# esp32buscam_03.net
KiCad netlist of a schematic drawn in EAGLE
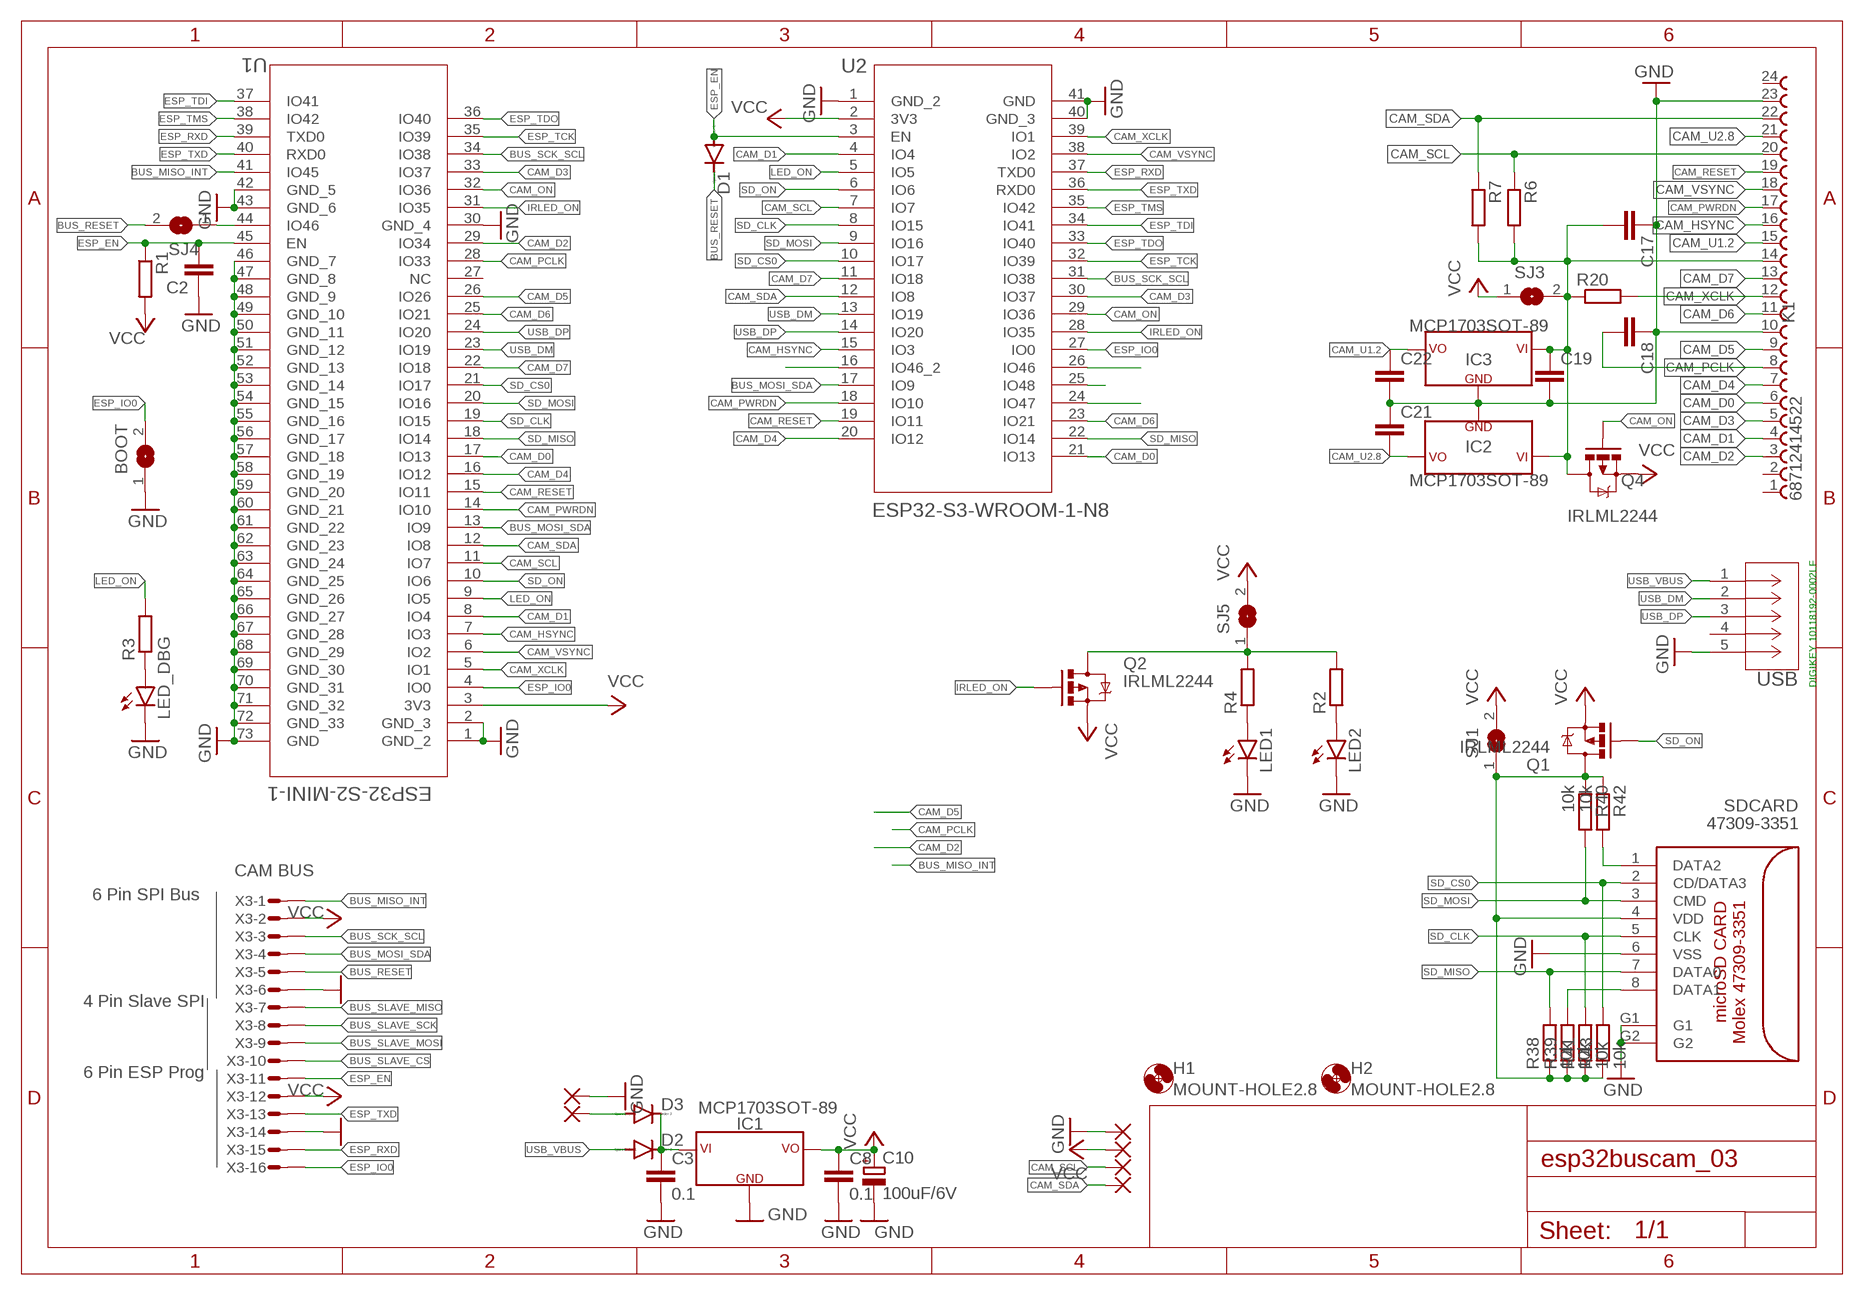
[diagram p0: schematic, sheet 1]

(export (version "E")
  (design (tool "Eeschema 10.0.6"))
  (components
    (comp (ref "BOOT")
      (value "SJ")
      (footprint "eagle-import:SJ")
      (libsource (lib "eagle-import") (part "SJ"))
    )
    (comp (ref "C2")
      (value "C-EUC0603")
      (footprint "eagle-import:C0603")
      (libsource (lib "eagle-import") (part "rcl_334_C-EUC0603"))
    )
    (comp (ref "C3")
      (value "0.1")
      (footprint "eagle-import:C0805")
      (libsource (lib "eagle-import") (part "C-EUC0805"))
    )
    (comp (ref "C8")
      (value "0.1")
      (footprint "eagle-import:C0805")
      (libsource (lib "eagle-import") (part "C-EUC0805"))
    )
    (comp (ref "C10")
      (value "100uF/6V")
      (footprint "eagle-import:B_3528-21R")
      (libsource (lib "eagle-import") (part "CPOL-EUB/3528-21R"))
    )
    (comp (ref "C17")
      (value "C-EUC0603")
      (footprint "eagle-import:C0603")
      (libsource (lib "eagle-import") (part "rcl_334_C-EUC0603"))
    )
    (comp (ref "C18")
      (value "C-EUC0603")
      (footprint "eagle-import:C0603")
      (libsource (lib "eagle-import") (part "rcl_334_C-EUC0603"))
    )
    (comp (ref "C19")
      (value "C-EUC0603")
      (footprint "eagle-import:C0603")
      (libsource (lib "eagle-import") (part "rcl_334_C-EUC0603"))
    )
    (comp (ref "C21")
      (value "C-EUC0603")
      (footprint "eagle-import:C0603")
      (libsource (lib "eagle-import") (part "rcl_334_C-EUC0603"))
    )
    (comp (ref "C22")
      (value "C-EUC0603")
      (footprint "eagle-import:C0603")
      (libsource (lib "eagle-import") (part "rcl_334_C-EUC0603"))
    )
    (comp (ref "D1")
      (value "DIODE-MINIMELF")
      (footprint "eagle-import:MINIMELF")
      (libsource (lib "eagle-import") (part "DIODE-MINIMELF"))
    )
    (comp (ref "D2")
      (value "DIODE-MINIMELF")
      (footprint "eagle-import:MINIMELF")
      (libsource (lib "eagle-import") (part "DIODE-MINIMELF"))
    )
    (comp (ref "D3")
      (value "DIODE-MINIMELF")
      (footprint "eagle-import:MINIMELF")
      (libsource (lib "eagle-import") (part "DIODE-MINIMELF"))
    )
    (comp (ref "H1")
      (value "MOUNT-HOLE2.8")
      (footprint "eagle-import:2,8")
      (libsource (lib "eagle-import") (part "MOUNT-HOLE2.8"))
    )
    (comp (ref "H2")
      (value "MOUNT-HOLE2.8")
      (footprint "eagle-import:2,8")
      (libsource (lib "eagle-import") (part "MOUNT-HOLE2.8"))
    )
    (comp (ref "IC1")
      (value "MCP1703SOT-89")
      (footprint "eagle-import:SOT89")
      (libsource (lib "eagle-import") (part "MCP1703SOT-89"))
    )
    (comp (ref "IC2")
      (value "MCP1703SOT-89")
      (footprint "eagle-import:SOT89")
      (libsource (lib "eagle-import") (part "MCP1703SOT-89"))
    )
    (comp (ref "IC3")
      (value "MCP1703SOT-89")
      (footprint "eagle-import:SOT89")
      (libsource (lib "eagle-import") (part "MCP1703SOT-89"))
    )
    (comp (ref "K1")
      (value "68712414522")
      (footprint "eagle-import:68712414522")
      (libsource (lib "eagle-import") (part "68712414522"))
    )
    (comp (ref "LED1")
      (value "LED5MM")
      (footprint "eagle-import:LED5MM")
      (libsource (lib "eagle-import") (part "LED5MM"))
    )
    (comp (ref "LED2")
      (value "LED5MM")
      (footprint "eagle-import:LED5MM")
      (libsource (lib "eagle-import") (part "LED5MM"))
    )
    (comp (ref "LED_DBG")
      (value "G")
      (footprint "eagle-import:CHIPLED_0805")
      (libsource (lib "eagle-import") (part "LEDCHIPLED_0805"))
    )
    (comp (ref "PAD1")
      (value "1,6/0,9")
      (footprint "eagle-import:1,6_0,9")
      (libsource (lib "eagle-import") (part "1,6/0,9"))
    )
    (comp (ref "PAD2")
      (value "1,6/0,9")
      (footprint "eagle-import:1,6_0,9")
      (libsource (lib "eagle-import") (part "1,6/0,9"))
    )
    (comp (ref "PAD3")
      (value "1,6/0,9")
      (footprint "eagle-import:1,6_0,9")
      (libsource (lib "eagle-import") (part "1,6/0,9"))
    )
    (comp (ref "PAD4")
      (value "1,6/0,9")
      (footprint "eagle-import:1,6_0,9")
      (libsource (lib "eagle-import") (part "1,6/0,9"))
    )
    (comp (ref "PAD5")
      (value "1,6/0,9")
      (footprint "eagle-import:1,6_0,9")
      (libsource (lib "eagle-import") (part "1,6/0,9"))
    )
    (comp (ref "PAD6")
      (value "1,6/0,9")
      (footprint "eagle-import:1,6_0,9")
      (libsource (lib "eagle-import") (part "1,6/0,9"))
    )
    (comp (ref "Q1")
      (value "IRLML2244")
      (footprint "eagle-import:SOT23-3")
      (libsource (lib "eagle-import") (part "MOSFET-PCHANNELIRLML2244"))
    )
    (comp (ref "Q2")
      (value "IRLML2244")
      (footprint "eagle-import:SOT23-3")
      (libsource (lib "eagle-import") (part "MOSFET-PCHANNELIRLML2244"))
    )
    (comp (ref "Q4")
      (value "IRLML2244")
      (footprint "eagle-import:SOT23-3")
      (libsource (lib "eagle-import") (part "MOSFET-PCHANNELIRLML2244"))
    )
    (comp (ref "R1")
      (value "R-EU_R0603")
      (footprint "eagle-import:R0603")
      (libsource (lib "eagle-import") (part "rcl_334_R-EU_R0603"))
    )
    (comp (ref "R2")
      (value "R-EU_R0402")
      (footprint "eagle-import:R0402")
      (libsource (lib "eagle-import") (part "rcl_334_R-EU_R0402"))
    )
    (comp (ref "R3")
      (value "R-EU_R0402")
      (footprint "eagle-import:R0402")
      (libsource (lib "eagle-import") (part "rcl_334_R-EU_R0402"))
    )
    (comp (ref "R4")
      (value "R-EU_R0402")
      (footprint "eagle-import:R0402")
      (libsource (lib "eagle-import") (part "rcl_334_R-EU_R0402"))
    )
    (comp (ref "R6")
      (value "R-EU_R0603")
      (footprint "eagle-import:R0603")
      (libsource (lib "eagle-import") (part "rcl_334_R-EU_R0603"))
    )
    (comp (ref "R7")
      (value "R-EU_R0603")
      (footprint "eagle-import:R0603")
      (libsource (lib "eagle-import") (part "rcl_334_R-EU_R0603"))
    )
    (comp (ref "R20")
      (value "R-EU_R0603")
      (footprint "eagle-import:R0603")
      (libsource (lib "eagle-import") (part "rcl_334_R-EU_R0603"))
    )
    (comp (ref "R38")
      (value "10k")
      (footprint "eagle-import:R0805")
      (libsource (lib "eagle-import") (part "R-EU_R0805"))
    )
    (comp (ref "R39")
      (value "10k")
      (footprint "eagle-import:R0805")
      (libsource (lib "eagle-import") (part "R-EU_R0805"))
    )
    (comp (ref "R40")
      (value "10k")
      (footprint "eagle-import:R0805")
      (libsource (lib "eagle-import") (part "R-EU_R0805"))
    )
    (comp (ref "R41")
      (value "10k")
      (footprint "eagle-import:R0805")
      (libsource (lib "eagle-import") (part "R-EU_R0805"))
    )
    (comp (ref "R42")
      (value "10k")
      (footprint "eagle-import:R0805")
      (libsource (lib "eagle-import") (part "R-EU_R0805"))
    )
    (comp (ref "R43")
      (value "10k")
      (footprint "eagle-import:R0805")
      (libsource (lib "eagle-import") (part "R-EU_R0805"))
    )
    (comp (ref "SDCARD")
      (value "47309-3351")
      (footprint "eagle-import:47309-3351")
      (libsource (lib "eagle-import") (part "47309-3351"))
    )
    (comp (ref "SJ1") (value "SJ") (footprint "eagle-import:SJ") (libsource (lib "eagle-import") (part "SJ")))
    (comp (ref "SJ3") (value "SJ") (footprint "eagle-import:SJ") (libsource (lib "eagle-import") (part "SJ")))
    (comp (ref "SJ4") (value "SJ") (footprint "eagle-import:SJ") (libsource (lib "eagle-import") (part "SJ")))
    (comp (ref "SJ5") (value "SJ") (footprint "eagle-import:SJ") (libsource (lib "eagle-import") (part "SJ")))
    (comp (ref "U1")
      (value "ESP32-S2-MINI-1")
      (footprint "eagle-import:QFN60_ESP32-S2-MINI-1_EXP")
      (fields (field (name "COPYRIGHT") "Copyright (C) 2018 Accelerated Designs. All rights reserved"))
      (libsource (lib "eagle-import") (part "ESP32-S2-MINI-1"))
    )
    (comp (ref "U2")
      (value "ESP32-S3-WROOM-1-N8")
      (footprint "eagle-import:ESP32-S3-WROOM-1-N8_EXP")
      (fields (field (name "COPYRIGHT") "Copyright (C) 2021 Ultra Librarian. All rights reserved."))
      (libsource (lib "eagle-import") (part "ESP32-S3-WROOM-1-N8"))
    )
    (comp (ref "USB")
      (value "10118192-0002LF")
      (footprint "eagle-import:CONN_10118192-0002LF_AMP")
      (fields (field (name "COPYRIGHT") "Copyright (C) 2018 Accelerated Designs. All rights reserved"))
      (libsource (lib "eagle-import") (part "10118192-0002LF"))
    )
    (comp (ref "X3")
      (value "CAM BUS")
      (footprint "eagle-import:MICROMATCH-16SMD")
      (libsource (lib "eagle-import") (part "MICROMATCH-16SMD"))
    )
  )
  (nets
    (net (code "1") (name "BUS_MISO_INT") (class "Default")
      (node (ref "U1") (pin "41") (pinfunction "IO45_41") (pintype "bidirectional"))
      (node (ref "X3") (pin "16") (pinfunction "S_16") (pintype "passive"))
    )
    (net (code "2") (name "BUS_MOSI_SDA") (class "Default")
      (node (ref "U1") (pin "13") (pinfunction "IO9_13") (pintype "bidirectional"))
      (node (ref "U2") (pin "17") (pinfunction "IO9_17") (pintype "passive"))
      (node (ref "X3") (pin "13") (pinfunction "S_13") (pintype "passive"))
    )
    (net (code "3") (name "BUS_RESET") (class "Default")
      (node (ref "D1") (pin "C") (pinfunction "C_C") (pintype "passive"))
      (node (ref "SJ4") (pin "2") (pinfunction "2_2") (pintype "passive"))
      (node (ref "X3") (pin "12") (pinfunction "S_12") (pintype "passive"))
    )
    (net (code "4") (name "BUS_SCK_SCL") (class "Default")
      (node (ref "U1") (pin "34") (pinfunction "IO38_34") (pintype "bidirectional"))
      (node (ref "U2") (pin "31") (pinfunction "IO38_31") (pintype "passive"))
      (node (ref "X3") (pin "14") (pinfunction "S_14") (pintype "passive"))
    )
    (net (code "5") (name "BUS_SLAVE_CS") (class "Default")
      (node (ref "X3") (pin "7") (pinfunction "S_7") (pintype "passive"))
    )
    (net (code "6") (name "BUS_SLAVE_MISO") (class "Default")
      (node (ref "X3") (pin "10") (pinfunction "S_10") (pintype "passive"))
    )
    (net (code "7") (name "BUS_SLAVE_MOSI") (class "Default")
      (node (ref "X3") (pin "8") (pinfunction "S_8") (pintype "passive"))
    )
    (net (code "8") (name "BUS_SLAVE_SCK") (class "Default")
      (node (ref "X3") (pin "9") (pinfunction "S_9") (pintype "passive"))
    )
    (net (code "9") (name "CAM_D0") (class "Default")
      (node (ref "K1") (pin "6") (pinfunction "6_6") (pintype "passive"))
      (node (ref "U1") (pin "17") (pinfunction "IO13_17") (pintype "bidirectional"))
      (node (ref "U2") (pin "21") (pinfunction "IO13_21") (pintype "passive"))
    )
    (net (code "10") (name "CAM_D1") (class "Default")
      (node (ref "K1") (pin "4") (pinfunction "4_4") (pintype "passive"))
      (node (ref "U1") (pin "8") (pinfunction "IO4_8") (pintype "bidirectional"))
      (node (ref "U2") (pin "4") (pinfunction "IO4_4") (pintype "passive"))
    )
    (net (code "11") (name "CAM_D2") (class "Default")
      (node (ref "K1") (pin "3") (pinfunction "3_3") (pintype "passive"))
      (node (ref "U1") (pin "29") (pinfunction "IO34_29") (pintype "bidirectional"))
    )
    (net (code "12") (name "CAM_D3") (class "Default")
      (node (ref "K1") (pin "5") (pinfunction "5_5") (pintype "passive"))
      (node (ref "U1") (pin "33") (pinfunction "IO37_33") (pintype "bidirectional"))
      (node (ref "U2") (pin "30") (pinfunction "IO37_30") (pintype "passive"))
    )
    (net (code "13") (name "CAM_D4") (class "Default")
      (node (ref "K1") (pin "7") (pinfunction "7_7") (pintype "passive"))
      (node (ref "U1") (pin "16") (pinfunction "IO12_16") (pintype "bidirectional"))
      (node (ref "U2") (pin "20") (pinfunction "IO12_20") (pintype "passive"))
    )
    (net (code "14") (name "CAM_D5") (class "Default")
      (node (ref "K1") (pin "9") (pinfunction "9_9") (pintype "passive"))
      (node (ref "U1") (pin "26") (pinfunction "IO26_26") (pintype "bidirectional"))
    )
    (net (code "15") (name "CAM_D6") (class "Default")
      (node (ref "K1") (pin "11") (pinfunction "11_11") (pintype "passive"))
      (node (ref "U1") (pin "25") (pinfunction "IO21_25") (pintype "bidirectional"))
      (node (ref "U2") (pin "23") (pinfunction "IO21_23") (pintype "passive"))
    )
    (net (code "16") (name "CAM_D7") (class "Default")
      (node (ref "K1") (pin "13") (pinfunction "13_13") (pintype "passive"))
      (node (ref "U1") (pin "22") (pinfunction "IO18_22") (pintype "bidirectional"))
      (node (ref "U2") (pin "11") (pinfunction "IO18_11") (pintype "passive"))
    )
    (net (code "17") (name "CAM_HSYNC") (class "Default")
      (node (ref "K1") (pin "16") (pinfunction "16_16") (pintype "passive"))
      (node (ref "U1") (pin "7") (pinfunction "IO3_7") (pintype "bidirectional"))
      (node (ref "U2") (pin "15") (pinfunction "IO3_15") (pintype "passive"))
    )
    (net (code "18") (name "CAM_ON") (class "Default")
      (node (ref "Q4") (pin "1") (pinfunction "G_1") (pintype "passive"))
      (node (ref "U1") (pin "32") (pinfunction "IO36_32") (pintype "bidirectional"))
      (node (ref "U2") (pin "29") (pinfunction "IO36_29") (pintype "passive"))
    )
    (net (code "19") (name "CAM_PCLK") (class "Default")
      (node (ref "C18") (pin "2") (pinfunction "2_2") (pintype "passive"))
      (node (ref "K1") (pin "8") (pinfunction "8_8") (pintype "passive"))
      (node (ref "U1") (pin "28") (pinfunction "IO33_28") (pintype "bidirectional"))
    )
    (net (code "20") (name "CAM_PWRDN") (class "Default")
      (node (ref "K1") (pin "17") (pinfunction "17_17") (pintype "passive"))
      (node (ref "U1") (pin "14") (pinfunction "IO10_14") (pintype "bidirectional"))
      (node (ref "U2") (pin "18") (pinfunction "IO10_18") (pintype "passive"))
    )
    (net (code "21") (name "CAM_RESET") (class "Default")
      (node (ref "K1") (pin "19") (pinfunction "19_19") (pintype "passive"))
      (node (ref "U1") (pin "15") (pinfunction "IO11_15") (pintype "bidirectional"))
      (node (ref "U2") (pin "19") (pinfunction "IO11_19") (pintype "passive"))
    )
    (net (code "22") (name "CAM_SCL") (class "Default")
      (node (ref "K1") (pin "20") (pinfunction "20_20") (pintype "passive"))
      (node (ref "PAD3") (pin "1") (pinfunction "P_1") (pintype "passive"))
      (node (ref "R6") (pin "1") (pinfunction "1_1") (pintype "passive"))
      (node (ref "U1") (pin "11") (pinfunction "IO7_11") (pintype "bidirectional"))
      (node (ref "U2") (pin "7") (pinfunction "IO7_7") (pintype "passive"))
    )
    (net (code "23") (name "CAM_SDA") (class "Default")
      (node (ref "K1") (pin "22") (pinfunction "22_22") (pintype "passive"))
      (node (ref "PAD4") (pin "1") (pinfunction "P_1") (pintype "passive"))
      (node (ref "R7") (pin "1") (pinfunction "1_1") (pintype "passive"))
      (node (ref "U1") (pin "12") (pinfunction "IO8_12") (pintype "bidirectional"))
      (node (ref "U2") (pin "12") (pinfunction "IO8_12") (pintype "passive"))
    )
    (net (code "24") (name "CAM_U1.2") (class "Default")
      (node (ref "C22") (pin "1") (pinfunction "1_1") (pintype "passive"))
      (node (ref "IC3") (pin "3") (pinfunction "VCC_3") (pintype "power_in"))
      (node (ref "K1") (pin "15") (pinfunction "15_15") (pintype "passive"))
    )
    (net (code "25") (name "CAM_U2.8") (class "Default")
      (node (ref "C21") (pin "2") (pinfunction "2_2") (pintype "passive"))
      (node (ref "IC2") (pin "3") (pinfunction "VCC_3") (pintype "power_in"))
      (node (ref "K1") (pin "21") (pinfunction "21_21") (pintype "passive"))
    )
    (net (code "26") (name "CAM_VSYNC") (class "Default")
      (node (ref "K1") (pin "18") (pinfunction "18_18") (pintype "passive"))
      (node (ref "U1") (pin "6") (pinfunction "IO2_6") (pintype "bidirectional"))
      (node (ref "U2") (pin "38") (pinfunction "IO2_38") (pintype "passive"))
    )
    (net (code "27") (name "CAM_XCLK") (class "Default")
      (node (ref "K1") (pin "12") (pinfunction "12_12") (pintype "passive"))
      (node (ref "R20") (pin "2") (pinfunction "2_2") (pintype "passive"))
      (node (ref "U1") (pin "5") (pinfunction "IO1_5") (pintype "bidirectional"))
      (node (ref "U2") (pin "39") (pinfunction "IO1_39") (pintype "passive"))
    )
    (net (code "28") (name "ESP_EN") (class "Default")
      (node (ref "C2") (pin "2") (pinfunction "2_2") (pintype "passive"))
      (node (ref "D1") (pin "A") (pinfunction "A_A") (pintype "passive"))
      (node (ref "R1") (pin "1") (pinfunction "1_1") (pintype "passive"))
      (node (ref "U1") (pin "45") (pinfunction "EN_45") (pintype "passive"))
      (node (ref "U2") (pin "3") (pinfunction "EN_3") (pintype "passive"))
      (node (ref "X3") (pin "6") (pinfunction "S_6") (pintype "passive"))
    )
    (net (code "29") (name "ESP_IO0") (class "Default")
      (node (ref "BOOT") (pin "2") (pinfunction "2_2") (pintype "passive"))
      (node (ref "U1") (pin "4") (pinfunction "IO0_4") (pintype "bidirectional"))
      (node (ref "U2") (pin "27") (pinfunction "IO0_27") (pintype "passive"))
      (node (ref "X3") (pin "1") (pinfunction "S_1") (pintype "passive"))
    )
    (net (code "30") (name "ESP_RXD") (class "Default")
      (node (ref "U1") (pin "39") (pinfunction "TXD0_39") (pintype "bidirectional"))
      (node (ref "U2") (pin "37") (pinfunction "TXD0_37") (pintype "passive"))
      (node (ref "X3") (pin "2") (pinfunction "S_2") (pintype "passive"))
    )
    (net (code "31") (name "ESP_TCK") (class "Default")
      (node (ref "U1") (pin "35") (pinfunction "IO39_35") (pintype "bidirectional"))
      (node (ref "U2") (pin "32") (pinfunction "IO39_32") (pintype "passive"))
    )
    (net (code "32") (name "ESP_TDI") (class "Default")
      (node (ref "U1") (pin "37") (pinfunction "IO41_37") (pintype "bidirectional"))
      (node (ref "U2") (pin "34") (pinfunction "IO41_34") (pintype "passive"))
    )
    (net (code "33") (name "ESP_TDO") (class "Default")
      (node (ref "U1") (pin "36") (pinfunction "IO40_36") (pintype "bidirectional"))
      (node (ref "U2") (pin "33") (pinfunction "IO40_33") (pintype "passive"))
    )
    (net (code "34") (name "ESP_TMS") (class "Default")
      (node (ref "U1") (pin "38") (pinfunction "IO42_38") (pintype "bidirectional"))
      (node (ref "U2") (pin "35") (pinfunction "IO42_35") (pintype "passive"))
    )
    (net (code "35") (name "ESP_TXD") (class "Default")
      (node (ref "U1") (pin "40") (pinfunction "RXD0_40") (pintype "bidirectional"))
      (node (ref "U2") (pin "36") (pinfunction "RXD0_36") (pintype "passive"))
      (node (ref "X3") (pin "4") (pinfunction "S_4") (pintype "passive"))
    )
    (net (code "36") (name "GND") (class "Default")
      (node (ref "BOOT") (pin "1") (pinfunction "1_1") (pintype "passive"))
      (node (ref "C10") (pin "-") (pinfunction "-_-") (pintype "passive"))
      (node (ref "C17") (pin "1") (pinfunction "1_1") (pintype "passive"))
      (node (ref "C18") (pin "1") (pinfunction "1_1") (pintype "passive"))
      (node (ref "C19") (pin "2") (pinfunction "2_2") (pintype "passive"))
      (node (ref "C2") (pin "1") (pinfunction "1_1") (pintype "passive"))
      (node (ref "C21") (pin "1") (pinfunction "1_1") (pintype "passive"))
      (node (ref "C22") (pin "2") (pinfunction "2_2") (pintype "passive"))
      (node (ref "C3") (pin "2") (pinfunction "2_2") (pintype "passive"))
      (node (ref "C8") (pin "2") (pinfunction "2_2") (pintype "passive"))
      (node (ref "IC1") (pin "1") (pinfunction "GND_1") (pintype "power_in"))
      (node (ref "IC2") (pin "1") (pinfunction "GND_1") (pintype "power_in"))
      (node (ref "IC3") (pin "1") (pinfunction "GND_1") (pintype "power_in"))
      (node (ref "K1") (pin "10") (pinfunction "10_10") (pintype "passive"))
      (node (ref "K1") (pin "23") (pinfunction "23_23") (pintype "passive"))
      (node (ref "LED1") (pin "K") (pinfunction "C_K") (pintype "passive"))
      (node (ref "LED2") (pin "K") (pinfunction "C_K") (pintype "passive"))
      (node (ref "LED_DBG") (pin "C") (pinfunction "C_C") (pintype "passive"))
      (node (ref "PAD1") (pin "1") (pinfunction "P_1") (pintype "passive"))
      (node (ref "PAD6") (pin "1") (pinfunction "P_1") (pintype "passive"))
      (node (ref "SDCARD") (pin "6") (pinfunction "VSS_6") (pintype "bidirectional"))
      (node (ref "SDCARD") (pin "G1") (pinfunction "G1_G1") (pintype "bidirectional"))
      (node (ref "SDCARD") (pin "G2") (pinfunction "G2_G2") (pintype "bidirectional"))
      (node (ref "U1") (pin "1") (pinfunction "GND_2_1") (pintype "passive"))
      (node (ref "U1") (pin "2") (pinfunction "GND_3_2") (pintype "passive"))
      (node (ref "U1") (pin "30") (pinfunction "GND_4_30") (pintype "passive"))
      (node (ref "U1") (pin "42") (pinfunction "GND_5_42") (pintype "passive"))
      (node (ref "U1") (pin "43") (pinfunction "GND_6_43") (pintype "passive"))
      (node (ref "U1") (pin "46") (pinfunction "GND_7_46") (pintype "passive"))
      (node (ref "U1") (pin "47") (pinfunction "GND_8_47") (pintype "passive"))
      (node (ref "U1") (pin "48") (pinfunction "GND_9_48") (pintype "passive"))
      (node (ref "U1") (pin "49") (pinfunction "GND_10_49") (pintype "passive"))
      (node (ref "U1") (pin "50") (pinfunction "GND_11_50") (pintype "passive"))
      (node (ref "U1") (pin "51") (pinfunction "GND_12_51") (pintype "passive"))
      (node (ref "U1") (pin "52") (pinfunction "GND_13_52") (pintype "passive"))
      (node (ref "U1") (pin "53") (pinfunction "GND_14_53") (pintype "passive"))
      (node (ref "U1") (pin "54") (pinfunction "GND_15_54") (pintype "passive"))
      (node (ref "U1") (pin "55") (pinfunction "GND_16_55") (pintype "passive"))
      (node (ref "U1") (pin "56") (pinfunction "GND_17_56") (pintype "passive"))
      (node (ref "U1") (pin "57") (pinfunction "GND_18_57") (pintype "passive"))
      (node (ref "U1") (pin "58") (pinfunction "GND_19_58") (pintype "passive"))
      (node (ref "U1") (pin "59") (pinfunction "GND_20_59") (pintype "passive"))
      (node (ref "U1") (pin "60") (pinfunction "GND_21_60") (pintype "passive"))
      (node (ref "U1") (pin "61") (pinfunction "GND_22_61") (pintype "passive"))
      (node (ref "U1") (pin "62") (pinfunction "GND_23_62") (pintype "passive"))
      (node (ref "U1") (pin "63") (pinfunction "GND_24_63") (pintype "passive"))
      (node (ref "U1") (pin "64") (pinfunction "GND_25_64") (pintype "passive"))
      (node (ref "U1") (pin "65") (pinfunction "GND_26_65") (pintype "passive"))
      (node (ref "U1") (pin "66") (pinfunction "GND_27_66") (pintype "passive"))
      (node (ref "U1") (pin "67") (pinfunction "GND_28_67") (pintype "passive"))
      (node (ref "U1") (pin "68") (pinfunction "GND_29_68") (pintype "passive"))
      (node (ref "U1") (pin "69") (pinfunction "GND_30_69") (pintype "passive"))
      (node (ref "U1") (pin "70") (pinfunction "GND_31_70") (pintype "passive"))
      (node (ref "U1") (pin "71") (pinfunction "GND_32_71") (pintype "passive"))
      (node (ref "U1") (pin "72") (pinfunction "GND_33_72") (pintype "passive"))
      (node (ref "U1") (pin "73") (pinfunction "GND_73") (pintype "passive"))
      (node (ref "U2") (pin "1") (pinfunction "GND_2_1") (pintype "passive"))
      (node (ref "U2") (pin "40") (pinfunction "GND_3_40") (pintype "passive"))
      (node (ref "U2") (pin "41") (pinfunction "GND_41") (pintype "passive"))
      (node (ref "USB") (pin "5") (pinfunction "5_5") (pintype "passive"))
      (node (ref "X3") (pin "11") (pinfunction "S_11") (pintype "passive"))
      (node (ref "X3") (pin "3") (pinfunction "S_3") (pintype "passive"))
    )
    (net (code "37") (name "IRLED_ON") (class "Default")
      (node (ref "Q2") (pin "1") (pinfunction "G_1") (pintype "passive"))
      (node (ref "U1") (pin "31") (pinfunction "IO35_31") (pintype "bidirectional"))
      (node (ref "U2") (pin "28") (pinfunction "IO35_28") (pintype "passive"))
    )
    (net (code "38") (name "LED_ON") (class "Default")
      (node (ref "R3") (pin "2") (pinfunction "2_2") (pintype "passive"))
      (node (ref "U1") (pin "9") (pinfunction "IO5_9") (pintype "bidirectional"))
      (node (ref "U2") (pin "5") (pinfunction "IO5_5") (pintype "passive"))
    )
    (net (code "39") (name "Net-(C3-Pad1)") (class "Default")
      (node (ref "C3") (pin "1") (pinfunction "1_1") (pintype "passive"))
      (node (ref "D2") (pin "C") (pinfunction "C_C") (pintype "passive"))
      (node (ref "D3") (pin "C") (pinfunction "C_C") (pintype "passive"))
      (node (ref "IC1") (pin "2") (pinfunction "VIN_2") (pintype "power_in"))
      (node (ref "IC1") (pin "4") (pinfunction "VIN_4") (pintype "power_in"))
    )
    (net (code "40") (name "Net-(LED1-PadA)") (class "Default")
      (node (ref "LED1") (pin "A") (pinfunction "A_A") (pintype "passive"))
      (node (ref "R4") (pin "1") (pinfunction "1_1") (pintype "passive"))
    )
    (net (code "41") (name "Net-(LED2-PadA)") (class "Default")
      (node (ref "LED2") (pin "A") (pinfunction "A_A") (pintype "passive"))
      (node (ref "R2") (pin "1") (pinfunction "1_1") (pintype "passive"))
    )
    (net (code "42") (name "Net-(LED_DBG-PadA)") (class "Default")
      (node (ref "LED_DBG") (pin "A") (pinfunction "A_A") (pintype "passive"))
      (node (ref "R3") (pin "1") (pinfunction "1_1") (pintype "passive"))
    )
    (net (code "43") (name "Net-(PAD5-P)") (class "Default")
      (node (ref "D3") (pin "A") (pinfunction "A_A") (pintype "passive"))
      (node (ref "PAD5") (pin "1") (pinfunction "P_1") (pintype "passive"))
    )
    (net (code "44") (name "Net-(Q1-D)") (class "Default")
      (node (ref "Q1") (pin "3") (pinfunction "D_3") (pintype "passive"))
      (node (ref "R38") (pin "1") (pinfunction "1_1") (pintype "passive"))
      (node (ref "R39") (pin "1") (pinfunction "1_1") (pintype "passive"))
      (node (ref "R40") (pin "1") (pinfunction "1_1") (pintype "passive"))
      (node (ref "R41") (pin "1") (pinfunction "1_1") (pintype "passive"))
      (node (ref "R42") (pin "1") (pinfunction "1_1") (pintype "passive"))
      (node (ref "R43") (pin "1") (pinfunction "1_1") (pintype "passive"))
      (node (ref "SDCARD") (pin "4") (pinfunction "VDD_4") (pintype "bidirectional"))
      (node (ref "SJ1") (pin "1") (pinfunction "1_1") (pintype "passive"))
    )
    (net (code "45") (name "Net-(Q2-D)") (class "Default")
      (node (ref "Q2") (pin "3") (pinfunction "D_3") (pintype "passive"))
      (node (ref "R2") (pin "2") (pinfunction "2_2") (pintype "passive"))
      (node (ref "R4") (pin "2") (pinfunction "2_2") (pintype "passive"))
      (node (ref "SJ5") (pin "1") (pinfunction "1_1") (pintype "passive"))
    )
    (net (code "46") (name "Net-(Q4-D)") (class "Default")
      (node (ref "C17") (pin "2") (pinfunction "2_2") (pintype "passive"))
      (node (ref "C19") (pin "1") (pinfunction "1_1") (pintype "passive"))
      (node (ref "IC2") (pin "2") (pinfunction "VIN_2") (pintype "power_in"))
      (node (ref "IC2") (pin "4") (pinfunction "VIN_4") (pintype "power_in"))
      (node (ref "IC3") (pin "2") (pinfunction "VIN_2") (pintype "power_in"))
      (node (ref "IC3") (pin "4") (pinfunction "VIN_4") (pintype "power_in"))
      (node (ref "K1") (pin "14") (pinfunction "14_14") (pintype "passive"))
      (node (ref "Q4") (pin "3") (pinfunction "D_3") (pintype "passive"))
      (node (ref "R20") (pin "1") (pinfunction "1_1") (pintype "passive"))
      (node (ref "R6") (pin "2") (pinfunction "2_2") (pintype "passive"))
      (node (ref "R7") (pin "2") (pinfunction "2_2") (pintype "passive"))
      (node (ref "SJ3") (pin "2") (pinfunction "2_2") (pintype "passive"))
    )
    (net (code "47") (name "Net-(SDCARD-DATA1)") (class "Default")
      (node (ref "R39") (pin "2") (pinfunction "2_2") (pintype "passive"))
      (node (ref "SDCARD") (pin "8") (pinfunction "DATA1_8") (pintype "bidirectional"))
    )
    (net (code "48") (name "Net-(SDCARD-DATA2)") (class "Default")
      (node (ref "R42") (pin "2") (pinfunction "2_2") (pintype "passive"))
      (node (ref "SDCARD") (pin "1") (pinfunction "DATA2_1") (pintype "bidirectional"))
    )
    (net (code "49") (name "Net-(U1-IO46)") (class "Default")
      (node (ref "SJ4") (pin "1") (pinfunction "1_1") (pintype "passive"))
      (node (ref "U1") (pin "44") (pinfunction "IO46_44") (pintype "bidirectional"))
    )
    (net (code "50") (name "SD_CLK") (class "Default")
      (node (ref "R41") (pin "2") (pinfunction "2_2") (pintype "passive"))
      (node (ref "SDCARD") (pin "5") (pinfunction "CLK_5") (pintype "bidirectional"))
      (node (ref "U1") (pin "19") (pinfunction "IO15_19") (pintype "bidirectional"))
      (node (ref "U2") (pin "8") (pinfunction "IO15_8") (pintype "passive"))
    )
    (net (code "51") (name "SD_CS0") (class "Default")
      (node (ref "R43") (pin "2") (pinfunction "2_2") (pintype "passive"))
      (node (ref "SDCARD") (pin "2") (pinfunction "CD/DATA3_2") (pintype "bidirectional"))
      (node (ref "U1") (pin "21") (pinfunction "IO17_21") (pintype "bidirectional"))
      (node (ref "U2") (pin "10") (pinfunction "IO17_10") (pintype "passive"))
    )
    (net (code "52") (name "SD_MISO") (class "Default")
      (node (ref "R38") (pin "2") (pinfunction "2_2") (pintype "passive"))
      (node (ref "SDCARD") (pin "7") (pinfunction "DATA0_7") (pintype "bidirectional"))
      (node (ref "U1") (pin "18") (pinfunction "IO14_18") (pintype "bidirectional"))
      (node (ref "U2") (pin "22") (pinfunction "IO14_22") (pintype "passive"))
    )
    (net (code "53") (name "SD_MOSI") (class "Default")
      (node (ref "R40") (pin "2") (pinfunction "2_2") (pintype "passive"))
      (node (ref "SDCARD") (pin "3") (pinfunction "CMD_3") (pintype "bidirectional"))
      (node (ref "U1") (pin "20") (pinfunction "IO16_20") (pintype "bidirectional"))
      (node (ref "U2") (pin "9") (pinfunction "IO16_9") (pintype "passive"))
    )
    (net (code "54") (name "SD_ON") (class "Default")
      (node (ref "Q1") (pin "1") (pinfunction "G_1") (pintype "passive"))
      (node (ref "U1") (pin "10") (pinfunction "IO6_10") (pintype "bidirectional"))
      (node (ref "U2") (pin "6") (pinfunction "IO6_6") (pintype "passive"))
    )
    (net (code "55") (name "USB_DM") (class "Default")
      (node (ref "U1") (pin "23") (pinfunction "IO19_23") (pintype "bidirectional"))
      (node (ref "U2") (pin "13") (pinfunction "IO19_13") (pintype "passive"))
      (node (ref "USB") (pin "2") (pinfunction "2_2") (pintype "passive"))
    )
    (net (code "56") (name "USB_DP") (class "Default")
      (node (ref "U1") (pin "24") (pinfunction "IO20_24") (pintype "bidirectional"))
      (node (ref "U2") (pin "14") (pinfunction "IO20_14") (pintype "passive"))
      (node (ref "USB") (pin "3") (pinfunction "3_3") (pintype "passive"))
    )
    (net (code "57") (name "USB_VBUS") (class "Default")
      (node (ref "D2") (pin "A") (pinfunction "A_A") (pintype "passive"))
      (node (ref "USB") (pin "1") (pinfunction "1_1") (pintype "passive"))
    )
    (net (code "58") (name "VCC") (class "Default")
      (node (ref "C10") (pin "+") (pinfunction "+_+") (pintype "passive"))
      (node (ref "C8") (pin "1") (pinfunction "1_1") (pintype "passive"))
      (node (ref "IC1") (pin "3") (pinfunction "VCC_3") (pintype "power_in"))
      (node (ref "PAD2") (pin "1") (pinfunction "P_1") (pintype "passive"))
      (node (ref "Q1") (pin "2") (pinfunction "S_2") (pintype "passive"))
      (node (ref "Q2") (pin "2") (pinfunction "S_2") (pintype "passive"))
      (node (ref "Q4") (pin "2") (pinfunction "S_2") (pintype "passive"))
      (node (ref "R1") (pin "2") (pinfunction "2_2") (pintype "passive"))
      (node (ref "SJ1") (pin "2") (pinfunction "2_2") (pintype "passive"))
      (node (ref "SJ3") (pin "1") (pinfunction "1_1") (pintype "passive"))
      (node (ref "SJ5") (pin "2") (pinfunction "2_2") (pintype "passive"))
      (node (ref "U1") (pin "3") (pinfunction "3V3_3") (pintype "passive"))
      (node (ref "U2") (pin "2") (pinfunction "3V3_2") (pintype "passive"))
      (node (ref "X3") (pin "15") (pinfunction "S_15") (pintype "passive"))
      (node (ref "X3") (pin "5") (pinfunction "S_5") (pintype "passive"))
    )
    (net (code "59") (name "unconnected-(K1-Pad1)") (class "Default")
      (node (ref "K1") (pin "1") (pinfunction "1_1") (pintype "passive"))
    )
    (net (code "60") (name "unconnected-(K1-Pad2)") (class "Default")
      (node (ref "K1") (pin "2") (pinfunction "2_2") (pintype "passive"))
    )
    (net (code "61") (name "unconnected-(K1-Pad24)") (class "Default")
      (node (ref "K1") (pin "24") (pinfunction "24_24") (pintype "passive"))
    )
    (net (code "62") (name "unconnected-(U1-NC-Pad27)") (class "Default")
      (node (ref "U1") (pin "27") (pinfunction "NC_27") (pintype "no_connect"))
    )
    (net (code "63") (name "unconnected-(U2-IO46-Pad26)") (class "Default")
      (node (ref "U2") (pin "26") (pinfunction "IO46_26") (pintype "passive"))
    )
    (net (code "64") (name "unconnected-(U2-IO46_2-Pad16)") (class "Default")
      (node (ref "U2") (pin "16") (pinfunction "IO46_2_16") (pintype "passive"))
    )
    (net (code "65") (name "unconnected-(U2-IO47-Pad24)") (class "Default")
      (node (ref "U2") (pin "24") (pinfunction "IO47_24") (pintype "passive"))
    )
    (net (code "66") (name "unconnected-(U2-IO48-Pad25)") (class "Default")
      (node (ref "U2") (pin "25") (pinfunction "IO48_25") (pintype "passive"))
    )
    (net (code "67") (name "unconnected-(USB-Pad4)") (class "Default")
      (node (ref "USB") (pin "4") (pinfunction "4_4") (pintype "passive"))
    )
  )
)
